# ARM_EURO_Platine6.net
KiCad netlist of a schematic drawn in Altium Designer
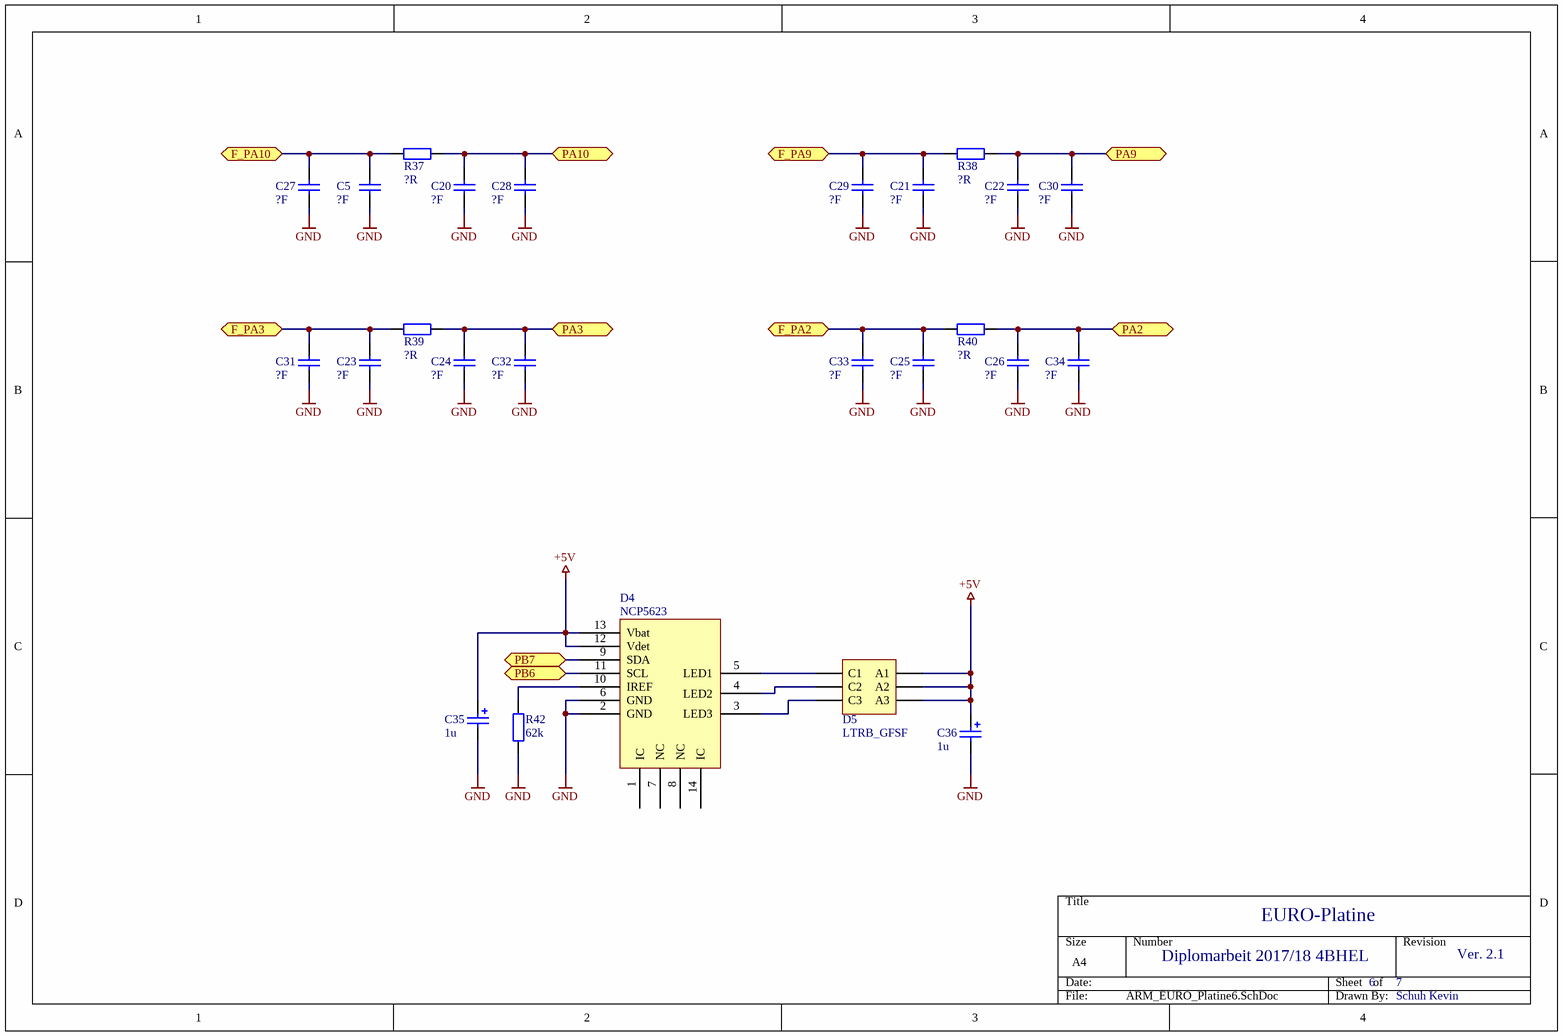
[diagram p0: ARM_EURO_Platine6.SchDoc]

(export (version "E")
  (design (tool "Eeschema 10.0.6"))
  (components
    (comp (ref "C5")
      (value "?F")
      (footprint "0603_CAP")
      (description "Capacitor_SMD")
      (fields (field (name "Comment") "Cap_Keramik_SMD") (field (name "PUBLISHER") "Altium Limited"))
      (libsource (lib "ARM_Libary_EURO") (part "Cap_Keramik_SMD"))
    )
    (comp (ref "C20")
      (value "?F")
      (footprint "0603_CAP")
      (description "Capacitor_SMD")
      (fields (field (name "Comment") "Cap_Keramik_SMD") (field (name "PUBLISHER") "Altium Limited"))
      (libsource (lib "ARM_Libary_EURO") (part "Cap_Keramik_SMD"))
    )
    (comp (ref "C21")
      (value "?F")
      (footprint "0603_CAP")
      (description "Capacitor_SMD")
      (fields (field (name "Comment") "Cap_Keramik_SMD") (field (name "PUBLISHER") "Altium Limited"))
      (libsource (lib "ARM_Libary_EURO") (part "Cap_Keramik_SMD"))
    )
    (comp (ref "C22")
      (value "?F")
      (footprint "0603_CAP")
      (description "Capacitor_SMD")
      (fields (field (name "Comment") "Cap_Keramik_SMD") (field (name "PUBLISHER") "Altium Limited"))
      (libsource (lib "ARM_Libary_EURO") (part "Cap_Keramik_SMD"))
    )
    (comp (ref "C23")
      (value "?F")
      (footprint "0603_CAP")
      (description "Capacitor_SMD")
      (fields (field (name "Comment") "Cap_Keramik_SMD") (field (name "PUBLISHER") "Altium Limited"))
      (libsource (lib "ARM_Libary_EURO") (part "Cap_Keramik_SMD"))
    )
    (comp (ref "C24")
      (value "?F")
      (footprint "0603_CAP")
      (description "Capacitor_SMD")
      (fields (field (name "Comment") "Cap_Keramik_SMD") (field (name "PUBLISHER") "Altium Limited"))
      (libsource (lib "ARM_Libary_EURO") (part "Cap_Keramik_SMD"))
    )
    (comp (ref "C25")
      (value "?F")
      (footprint "0603_CAP")
      (description "Capacitor_SMD")
      (fields (field (name "Comment") "Cap_Keramik_SMD") (field (name "PUBLISHER") "Altium Limited"))
      (libsource (lib "ARM_Libary_EURO") (part "Cap_Keramik_SMD"))
    )
    (comp (ref "C26")
      (value "?F")
      (footprint "0603_CAP")
      (description "Capacitor_SMD")
      (fields (field (name "Comment") "Cap_Keramik_SMD") (field (name "PUBLISHER") "Altium Limited"))
      (libsource (lib "ARM_Libary_EURO") (part "Cap_Keramik_SMD"))
    )
    (comp (ref "C27")
      (value "?F")
      (footprint "0603_CAP")
      (description "Capacitor_SMD")
      (fields (field (name "Comment") "Cap_Keramik_SMD") (field (name "PUBLISHER") "Altium Limited"))
      (libsource (lib "ARM_Libary_EURO") (part "Cap_Keramik_SMD"))
    )
    (comp (ref "C28")
      (value "?F")
      (footprint "0603_CAP")
      (description "Capacitor_SMD")
      (fields (field (name "Comment") "Cap_Keramik_SMD") (field (name "PUBLISHER") "Altium Limited"))
      (libsource (lib "ARM_Libary_EURO") (part "Cap_Keramik_SMD"))
    )
    (comp (ref "C29")
      (value "?F")
      (footprint "0603_CAP")
      (description "Capacitor_SMD")
      (fields (field (name "Comment") "Cap_Keramik_SMD") (field (name "PUBLISHER") "Altium Limited"))
      (libsource (lib "ARM_Libary_EURO") (part "Cap_Keramik_SMD"))
    )
    (comp (ref "C30")
      (value "?F")
      (footprint "0603_CAP")
      (description "Capacitor_SMD")
      (fields (field (name "Comment") "Cap_Keramik_SMD") (field (name "PUBLISHER") "Altium Limited"))
      (libsource (lib "ARM_Libary_EURO") (part "Cap_Keramik_SMD"))
    )
    (comp (ref "C31")
      (value "?F")
      (footprint "0603_CAP")
      (description "Capacitor_SMD")
      (fields (field (name "Comment") "Cap_Keramik_SMD") (field (name "PUBLISHER") "Altium Limited"))
      (libsource (lib "ARM_Libary_EURO") (part "Cap_Keramik_SMD"))
    )
    (comp (ref "C32")
      (value "?F")
      (footprint "0603_CAP")
      (description "Capacitor_SMD")
      (fields (field (name "Comment") "Cap_Keramik_SMD") (field (name "PUBLISHER") "Altium Limited"))
      (libsource (lib "ARM_Libary_EURO") (part "Cap_Keramik_SMD"))
    )
    (comp (ref "C33")
      (value "?F")
      (footprint "0603_CAP")
      (description "Capacitor_SMD")
      (fields (field (name "Comment") "Cap_Keramik_SMD") (field (name "PUBLISHER") "Altium Limited"))
      (libsource (lib "ARM_Libary_EURO") (part "Cap_Keramik_SMD"))
    )
    (comp (ref "C34")
      (value "?F")
      (footprint "0603_CAP")
      (description "Capacitor_SMD")
      (fields (field (name "Comment") "Cap_Keramik_SMD") (field (name "PUBLISHER") "Altium Limited"))
      (libsource (lib "ARM_Libary_EURO") (part "Cap_Keramik_SMD"))
    )
    (comp (ref "C35")
      (value "1u")
      (footprint "1411_Cap_Pol_Tantal")
      (description "Polarized Capacitor")
      (fields (field (name "Comment") "Cap_Pol_Tantal") (field (name "PUBLISHER") "Altium Limited"))
      (libsource (lib "ARM_Libary_EURO") (part "Cap_Pol_Tantal"))
    )
    (comp (ref "C36")
      (value "1u")
      (footprint "1411_Cap_Pol_Tantal")
      (description "Polarized Capacitor")
      (fields (field (name "Comment") "Cap_Pol_Tantal") (field (name "PUBLISHER") "Altium Limited"))
      (libsource (lib "ARM_Libary_EURO") (part "Cap_Pol_Tantal"))
    )
    (comp (ref "D4")
      (value "NCP5623")
      (footprint "NCP5623")
      (libsource (lib "ARM_Libary_EURO") (part "NCP5623"))
    )
    (comp (ref "D5")
      (value "LTRB_GFSF")
      (footprint "LTRB_GFSF")
      (description "LTRB-GFSF")
      (fields (field (name "PUBLISHER") "Altium Limited"))
      (libsource (lib "ARM_Libary_EURO") (part "LTRB_GFSF"))
    )
    (comp (ref "R37")
      (value "?R")
      (footprint "0603_Res")
      (description "Resistor")
      (fields (field (name "Comment") "Res_SMD") (field (name "PUBLISHER") "Altium Limited"))
      (libsource (lib "ARM_Libary_EURO") (part "Res_SMD"))
    )
    (comp (ref "R38")
      (value "?R")
      (footprint "0603_Res")
      (description "Resistor")
      (fields (field (name "Comment") "Res_SMD") (field (name "PUBLISHER") "Altium Limited"))
      (libsource (lib "ARM_Libary_EURO") (part "Res_SMD"))
    )
    (comp (ref "R39")
      (value "?R")
      (footprint "0603_Res")
      (description "Resistor")
      (fields (field (name "Comment") "Res_SMD") (field (name "PUBLISHER") "Altium Limited"))
      (libsource (lib "ARM_Libary_EURO") (part "Res_SMD"))
    )
    (comp (ref "R40")
      (value "?R")
      (footprint "0603_Res")
      (description "Resistor")
      (fields (field (name "Comment") "Res_SMD") (field (name "PUBLISHER") "Altium Limited"))
      (libsource (lib "ARM_Libary_EURO") (part "Res_SMD"))
    )
    (comp (ref "R42")
      (value "62k")
      (footprint "0805_Res")
      (description "Resistor")
      (fields (field (name "Comment") "Res_SMD") (field (name "PUBLISHER") "Altium Limited"))
      (libsource (lib "") (part "Res_SMD_1"))
    )
  )
  (nets
    (net (code "1") (name "+5V") (class "Default")
      (node (ref "C35") (pin "1") (pinfunction "1_1") (pintype "passive"))
      (node (ref "C36") (pin "1") (pinfunction "1_1") (pintype "passive"))
      (node (ref "D4") (pin "12") (pinfunction "Vdet_12") (pintype "passive"))
      (node (ref "D4") (pin "13") (pinfunction "Vbat_13") (pintype "passive"))
      (node (ref "D5") (pin "4") (pinfunction "A3_4") (pintype "passive"))
      (node (ref "D5") (pin "5") (pinfunction "A2_5") (pintype "passive"))
      (node (ref "D5") (pin "6") (pinfunction "A1_6") (pintype "passive"))
    )
    (net (code "2") (name "/F_PA2") (class "Default")
      (node (ref "C25") (pin "2") (pinfunction "2_2") (pintype "passive"))
      (node (ref "C33") (pin "2") (pinfunction "2_2") (pintype "passive"))
      (node (ref "R40") (pin "1") (pinfunction "1_1") (pintype "passive"))
    )
    (net (code "3") (name "/F_PA3") (class "Default")
      (node (ref "C23") (pin "2") (pinfunction "2_2") (pintype "passive"))
      (node (ref "C31") (pin "2") (pinfunction "2_2") (pintype "passive"))
      (node (ref "R39") (pin "1") (pinfunction "1_1") (pintype "passive"))
    )
    (net (code "4") (name "/F_PA9") (class "Default")
      (node (ref "C21") (pin "2") (pinfunction "2_2") (pintype "passive"))
      (node (ref "C29") (pin "2") (pinfunction "2_2") (pintype "passive"))
      (node (ref "R38") (pin "1") (pinfunction "1_1") (pintype "passive"))
    )
    (net (code "5") (name "/F_PA10") (class "Default")
      (node (ref "C27") (pin "2") (pinfunction "2_2") (pintype "passive"))
      (node (ref "C5") (pin "2") (pinfunction "2_2") (pintype "passive"))
      (node (ref "R37") (pin "1") (pinfunction "1_1") (pintype "passive"))
    )
    (net (code "6") (name "/PA2") (class "Default")
      (node (ref "C26") (pin "2") (pinfunction "2_2") (pintype "passive"))
      (node (ref "C34") (pin "2") (pinfunction "2_2") (pintype "passive"))
      (node (ref "R40") (pin "2") (pinfunction "2_2") (pintype "passive"))
    )
    (net (code "7") (name "/PA3") (class "Default")
      (node (ref "C24") (pin "2") (pinfunction "2_2") (pintype "passive"))
      (node (ref "C32") (pin "2") (pinfunction "2_2") (pintype "passive"))
      (node (ref "R39") (pin "2") (pinfunction "2_2") (pintype "passive"))
    )
    (net (code "8") (name "/PA9") (class "Default")
      (node (ref "C22") (pin "2") (pinfunction "2_2") (pintype "passive"))
      (node (ref "C30") (pin "2") (pinfunction "2_2") (pintype "passive"))
      (node (ref "R38") (pin "2") (pinfunction "2_2") (pintype "passive"))
    )
    (net (code "9") (name "/PA10") (class "Default")
      (node (ref "C20") (pin "2") (pinfunction "2_2") (pintype "passive"))
      (node (ref "C28") (pin "2") (pinfunction "2_2") (pintype "passive"))
      (node (ref "R37") (pin "2") (pinfunction "2_2") (pintype "passive"))
    )
    (net (code "10") (name "/PB6") (class "Default")
      (node (ref "D4") (pin "11") (pinfunction "SCL_11") (pintype "passive"))
    )
    (net (code "11") (name "/PB7") (class "Default")
      (node (ref "D4") (pin "9") (pinfunction "SDA_9") (pintype "passive"))
    )
    (net (code "12") (name "GND") (class "Default")
      (node (ref "C20") (pin "1") (pinfunction "1_1") (pintype "passive"))
      (node (ref "C21") (pin "1") (pinfunction "1_1") (pintype "passive"))
      (node (ref "C22") (pin "1") (pinfunction "1_1") (pintype "passive"))
      (node (ref "C23") (pin "1") (pinfunction "1_1") (pintype "passive"))
      (node (ref "C24") (pin "1") (pinfunction "1_1") (pintype "passive"))
      (node (ref "C25") (pin "1") (pinfunction "1_1") (pintype "passive"))
      (node (ref "C26") (pin "1") (pinfunction "1_1") (pintype "passive"))
      (node (ref "C27") (pin "1") (pinfunction "1_1") (pintype "passive"))
      (node (ref "C28") (pin "1") (pinfunction "1_1") (pintype "passive"))
      (node (ref "C29") (pin "1") (pinfunction "1_1") (pintype "passive"))
      (node (ref "C30") (pin "1") (pinfunction "1_1") (pintype "passive"))
      (node (ref "C31") (pin "1") (pinfunction "1_1") (pintype "passive"))
      (node (ref "C32") (pin "1") (pinfunction "1_1") (pintype "passive"))
      (node (ref "C33") (pin "1") (pinfunction "1_1") (pintype "passive"))
      (node (ref "C34") (pin "1") (pinfunction "1_1") (pintype "passive"))
      (node (ref "C35") (pin "2") (pinfunction "2_2") (pintype "passive"))
      (node (ref "C36") (pin "2") (pinfunction "2_2") (pintype "passive"))
      (node (ref "C5") (pin "1") (pinfunction "1_1") (pintype "passive"))
      (node (ref "D4") (pin "2") (pinfunction "GND_2") (pintype "passive"))
      (node (ref "D4") (pin "6") (pinfunction "GND_6") (pintype "passive"))
      (node (ref "R42") (pin "1") (pinfunction "1_1") (pintype "passive"))
    )
    (net (code "13") (name "Net-(D4-IREF)") (class "Default")
      (node (ref "D4") (pin "10") (pinfunction "IREF_10") (pintype "passive"))
      (node (ref "R42") (pin "2") (pinfunction "2_2") (pintype "passive"))
    )
    (net (code "14") (name "Net-(D4-LED1)") (class "Default")
      (node (ref "D4") (pin "5") (pinfunction "LED1_5") (pintype "passive"))
      (node (ref "D5") (pin "1") (pinfunction "C1_1") (pintype "passive"))
    )
    (net (code "15") (name "Net-(D4-LED2)") (class "Default")
      (node (ref "D4") (pin "4") (pinfunction "LED2_4") (pintype "passive"))
      (node (ref "D5") (pin "2") (pinfunction "C2_2") (pintype "passive"))
    )
    (net (code "16") (name "Net-(D4-LED3)") (class "Default")
      (node (ref "D4") (pin "3") (pinfunction "LED3_3") (pintype "passive"))
      (node (ref "D5") (pin "3") (pinfunction "C3_3") (pintype "passive"))
    )
    (net (code "17") (name "unconnected-(D4-IC-Pad1)") (class "Default")
      (node (ref "D4") (pin "1") (pinfunction "IC_1") (pintype "passive"))
    )
    (net (code "18") (name "unconnected-(D4-IC-Pad14)") (class "Default")
      (node (ref "D4") (pin "14") (pinfunction "IC_14") (pintype "passive"))
    )
    (net (code "19") (name "unconnected-(D4-NC-Pad7)") (class "Default")
      (node (ref "D4") (pin "7") (pinfunction "NC_7") (pintype "passive"))
    )
    (net (code "20") (name "unconnected-(D4-NC-Pad8)") (class "Default")
      (node (ref "D4") (pin "8") (pinfunction "NC_8") (pintype "passive"))
    )
  )
)
